# UNO-TH_Rev3e.net
KiCad netlist of a schematic drawn in Altium Designer
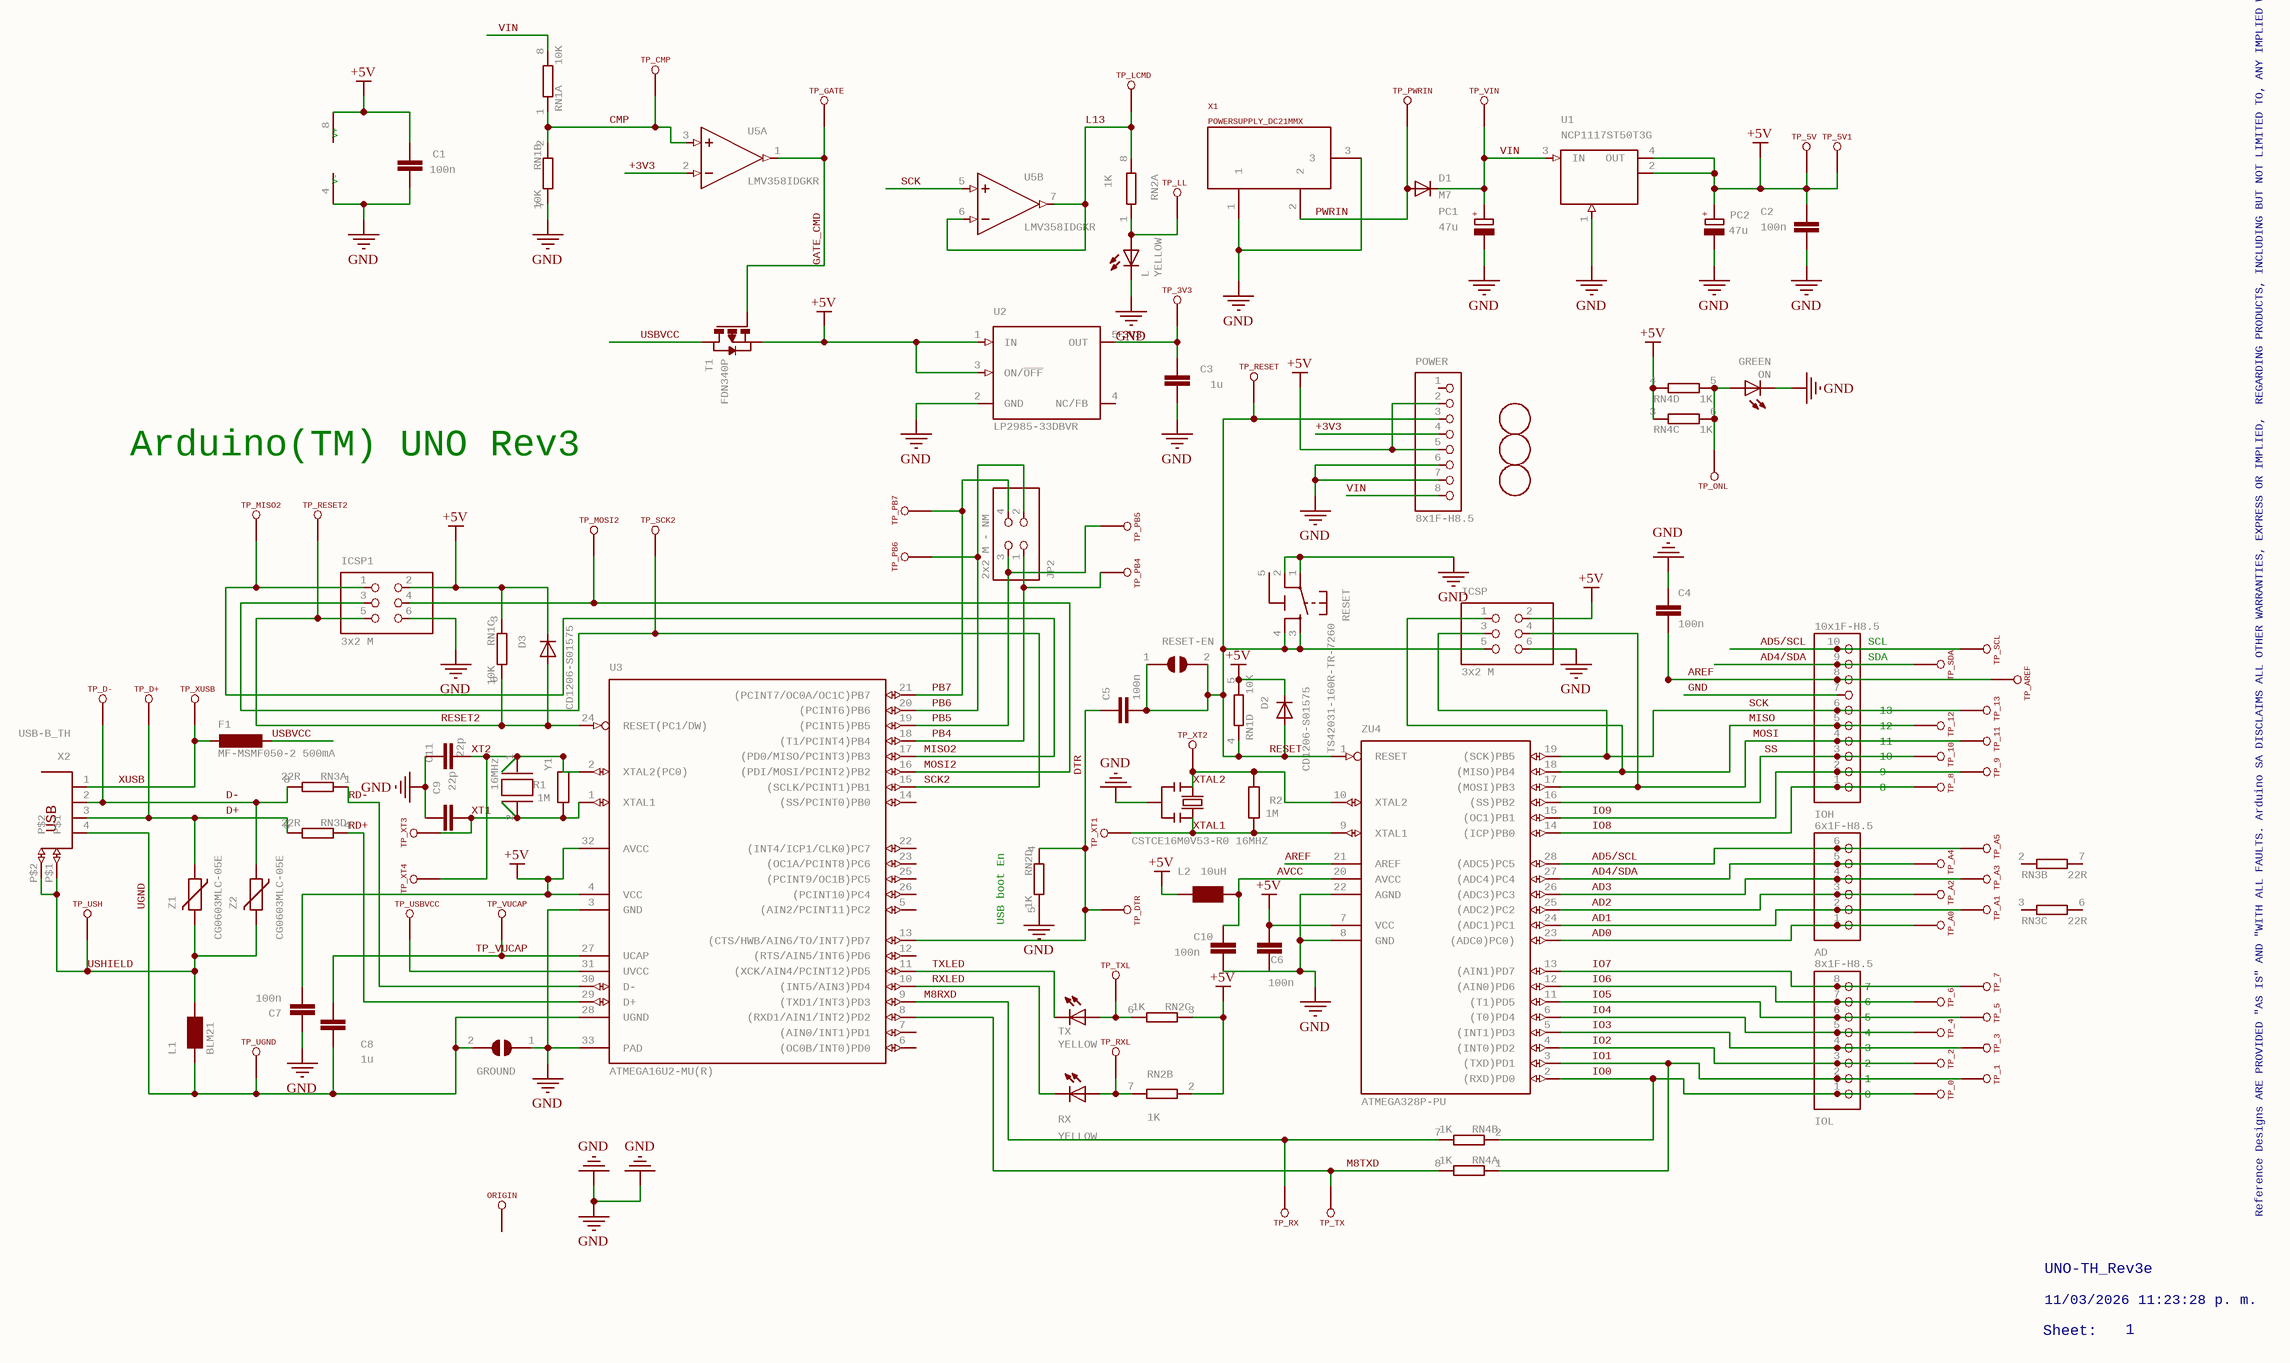
[diagram p0: UNO-TH_Rev3e.SchDoc]

(export (version "E")
  (design (tool "Eeschema 10.0.6"))
  (components
    (comp (ref "AD")
      (value "6x1F-H8.5")
      (footprint "1X06")
      (description "PIN HEADER")
      (libsource (lib "SmartPrj") (part "PINHD-1X6"))
    )
    (comp (ref "C1")
      (value "100n")
      (footprint "C0603-ROUND")
      (description "CAPACITOR, European symbol")
      (libsource (lib "") (part "C-EU0603-RND_3"))
    )
    (comp (ref "C2")
      (value "100n")
      (footprint "C0603-ROUND")
      (description "CAPACITOR, European symbol")
      (libsource (lib "") (part "C-EU0603-RND_2"))
    )
    (comp (ref "C3")
      (value "1u")
      (footprint "C0603-ROUND")
      (description "CAPACITOR, European symbol")
      (libsource (lib "") (part "C-EU0603-RND_3"))
    )
    (comp (ref "C4")
      (value "100n")
      (footprint "C0603-ROUND")
      (description "CAPACITOR, European symbol")
      (libsource (lib "") (part "C-EU0603-RND_1"))
    )
    (comp (ref "C5")
      (value "100n")
      (footprint "C0603-ROUND")
      (description "CAPACITOR, European symbol")
      (libsource (lib "") (part "C-EU0603-RND_3"))
    )
    (comp (ref "C6")
      (value "100n")
      (footprint "C0603-ROUND")
      (description "CAPACITOR, European symbol")
      (libsource (lib "") (part "C-EU0603-RND_2"))
    )
    (comp (ref "C7")
      (value "100n")
      (footprint "C0603-ROUND")
      (description "CAPACITOR, European symbol")
      (libsource (lib "SmartPrj") (part "C-EU0603-RND"))
    )
    (comp (ref "C8")
      (value "1u")
      (footprint "C0603-ROUND")
      (description "CAPACITOR, European symbol")
      (libsource (lib "SmartPrj") (part "C-EU0603-RND"))
    )
    (comp (ref "C9")
      (value "22p")
      (footprint "C0603-ROUND")
      (description "CAPACITOR, European symbol")
      (libsource (lib "") (part "C-EU0603-RND_1"))
    )
    (comp (ref "C10")
      (value "100n")
      (footprint "C0603-ROUND")
      (description "CAPACITOR, European symbol")
      (libsource (lib "") (part "C-EU0603-RND_2"))
    )
    (comp (ref "C11")
      (value "22p")
      (footprint "C0603-ROUND")
      (description "CAPACITOR, European symbol")
      (libsource (lib "") (part "C-EU0603-RND_1"))
    )
    (comp (ref "D1")
      (value "M7")
      (footprint "SMB")
      (description "DIODE")
      (libsource (lib "diode") (part "DIODE-SMB"))
    )
    (comp (ref "D2")
      (value "CD1206-S01575")
      (footprint "MINIMELF")
      (description "DIODE")
      (libsource (lib "diode") (part "DIODE-MINIMELF"))
    )
    (comp (ref "D3")
      (value "CD1206-S01575")
      (footprint "MINIMELF")
      (description "DIODE")
      (libsource (lib "diode") (part "DIODE-MINIMELF"))
    )
    (comp (ref "F1")
      (value "MF-MSMF050-2 500mA")
      (footprint "L1812")
      (description "INDUCTOR, European symbol")
      (libsource (lib "rcl") (part "L-EUL1812"))
    )
    (comp (ref "FD1")
      (value "FIDUCIALMOUNT")
      (footprint "FIDUCIA-MOUNT")
      (libsource (lib "SmartPrj") (part "FIDUCIALMOUNT"))
    )
    (comp (ref "FD2")
      (value "FIDUCIALMOUNT")
      (footprint "FIDUCIA-MOUNT")
      (libsource (lib "SmartPrj") (part "FIDUCIALMOUNT"))
    )
    (comp (ref "FD3")
      (value "FIDUCIALMOUNT")
      (footprint "FIDUCIA-MOUNT")
      (libsource (lib "SmartPrj") (part "FIDUCIALMOUNT"))
    )
    (comp (ref "GROUND")
      (value "SJ")
      (footprint "SJ")
      (description "SMD solder JUMPER")
      (libsource (lib "jumper") (part "SJ"))
    )
    (comp (ref "ICSP")
      (value "3x2 M")
      (footprint "2X03")
      (description "PIN HEADER")
      (libsource (lib "SmartPrj") (part "PINHD-2X3"))
    )
    (comp (ref "ICSP1")
      (value "3x2 M")
      (footprint "2X03")
      (description "PIN HEADER")
      (libsource (lib "SmartPrj") (part "PINHD-2X3"))
    )
    (comp (ref "IOH")
      (value "10x1F-H8.5")
      (footprint "1X10")
      (description "PIN HEADER")
      (libsource (lib "SmartPrj") (part "PINHD-1X10_ARD"))
    )
    (comp (ref "IOL")
      (value "8x1F-H8.5")
      (footprint "1X08")
      (description "PIN HEADER")
      (libsource (lib "SmartPrj") (part "PINHD-1X8"))
    )
    (comp (ref "JP2")
      (value "2x2 M - NM")
      (footprint "2X02")
      (description "PIN HEADER")
      (libsource (lib "SmartPrj") (part "PINHD-2X2"))
    )
    (comp (ref "L")
      (value "YELLOW")
      (footprint "CHIP-LED0805")
      (libsource (lib "led") (part "LEDCHIP-LED0805"))
    )
    (comp (ref "L1")
      (value "BLM21")
      (footprint "0805")
      (libsource (lib "wuerth-elektronik") (part "WE-CBF_0805"))
    )
    (comp (ref "L2")
      (value "10uH")
      (footprint "0805")
      (description "10uH 0805")
      (fields (field (name "PART_NUMBER") "CV201210-100K"))
      (libsource (lib "Induttanze") (part "0715_CV201210-100K"))
    )
    (comp (ref "ON")
      (value "GREEN")
      (footprint "CHIP-LED0805")
      (libsource (lib "led") (part "LEDCHIP-LED0805"))
    )
    (comp (ref "ORIGIN") (value "TP_SP") (footprint "TP-SP") (libsource (lib "SmartPrj") (part "TP_SP")))
    (comp (ref "PC1")
      (value "47u")
      (footprint "PANASONIC_D")
      (description "POLARIZED CAPACITOR, European symbol")
      (fields (field (name "+") "+"))
      (libsource (lib "rcl") (part "CPOL-EUD"))
    )
    (comp (ref "PC2")
      (value "47u")
      (footprint "PANASONIC_D")
      (description "POLARIZED CAPACITOR, European symbol")
      (fields (field (name "+") "+"))
      (libsource (lib "rcl") (part "CPOL-EUD"))
    )
    (comp (ref "POWER")
      (value "8x1F-H8.5")
      (footprint "1X08")
      (description "PIN HEADER")
      (libsource (lib "SmartPrj") (part "PINHD-1X8"))
    )
    (comp (ref "R1")
      (value "1M")
      (footprint "R0603-ROUND")
      (description "RESISTOR, European symbol")
      (libsource (lib "SmartPrj") (part "R-EU_R0603"))
    )
    (comp (ref "R2")
      (value "1M")
      (footprint "R0603-ROUND")
      (description "RESISTOR, European symbol")
      (libsource (lib "SmartPrj") (part "R-EU_R0603"))
    )
    (comp (ref "RESET")
      (value "TS42031-160R-TR-7260")
      (footprint "TS42")
      (description "TS42 Dongnan Electronics Tact switch VDC 12V - 50mA")
      (libsource (lib "SmartPrj") (part "TS42"))
    )
    (comp (ref "RESET-EN")
      (value "SJ")
      (footprint "SJ")
      (description "SMD solder JUMPER")
      (libsource (lib "jumper") (part "SJ"))
    )
    (comp (ref "RN1")
      (value "10K")
      (footprint "CAY16")
      (description "Array Chip Resistor   Source: RS Component / Phycomp")
      (libsource (lib "resistor-dil") (part "4R-NCAY16"))
    )
    (comp (ref "RN2")
      (value "1K")
      (footprint "CAY16")
      (description "Array Chip Resistor   Source: RS Component / Phycomp")
      (libsource (lib "resistor-dil") (part "4R-NCAY16"))
    )
    (comp (ref "RN3")
      (value "22R")
      (footprint "CAY16")
      (description "Array Chip Resistor   Source: RS Component / Phycomp")
      (libsource (lib "resistor-dil") (part "4R-NCAY16"))
    )
    (comp (ref "RN4")
      (value "1K")
      (footprint "CAY16")
      (description "Array Chip Resistor   Source: RS Component / Phycomp")
      (libsource (lib "resistor-dil") (part "4R-NCAY16"))
    )
    (comp (ref "RX")
      (value "YELLOW")
      (footprint "CHIP-LED0805")
      (libsource (lib "led") (part "LEDCHIP-LED0805"))
    )
    (comp (ref "T1")
      (value "FDN340P")
      (footprint "SOT-23")
      (description "MOS FET")
      (libsource (lib "zetex") (part "PMOSSOT23"))
    )
    (comp (ref "TP_0") (value "TP_SP") (footprint "TP-SP") (libsource (lib "SmartPrj") (part "TP_SP")))
    (comp (ref "TP_1") (value "TP_SP") (footprint "TP-SP") (libsource (lib "SmartPrj") (part "TP_SP")))
    (comp (ref "TP_2") (value "TP_SP") (footprint "TP-SP") (libsource (lib "SmartPrj") (part "TP_SP")))
    (comp (ref "TP_3") (value "TP_SP") (footprint "TP-SP") (libsource (lib "SmartPrj") (part "TP_SP")))
    (comp (ref "TP_3V3") (value "TP_SP") (footprint "TP-SP") (libsource (lib "SmartPrj") (part "TP_SP")))
    (comp (ref "TP_4") (value "TP_SP") (footprint "TP-SP") (libsource (lib "SmartPrj") (part "TP_SP")))
    (comp (ref "TP_5") (value "TP_SP") (footprint "TP-SP") (libsource (lib "SmartPrj") (part "TP_SP")))
    (comp (ref "TP_5V") (value "TP_SP") (footprint "TP-SP") (libsource (lib "SmartPrj") (part "TP_SP")))
    (comp (ref "TP_5V1") (value "TP_SP") (footprint "TP-SP") (libsource (lib "SmartPrj") (part "TP_SP")))
    (comp (ref "TP_6") (value "TP_SP") (footprint "TP-SP") (libsource (lib "SmartPrj") (part "TP_SP")))
    (comp (ref "TP_7") (value "TP_SP") (footprint "TP-SP") (libsource (lib "SmartPrj") (part "TP_SP")))
    (comp (ref "TP_8") (value "TP_SP") (footprint "TP-SP") (libsource (lib "SmartPrj") (part "TP_SP")))
    (comp (ref "TP_9") (value "TP_SP") (footprint "TP-SP") (libsource (lib "SmartPrj") (part "TP_SP")))
    (comp (ref "TP_10") (value "TP_SP") (footprint "TP-SP") (libsource (lib "SmartPrj") (part "TP_SP")))
    (comp (ref "TP_11") (value "TP_SP") (footprint "TP-SP") (libsource (lib "SmartPrj") (part "TP_SP")))
    (comp (ref "TP_12") (value "TP_SP") (footprint "TP-SP") (libsource (lib "SmartPrj") (part "TP_SP")))
    (comp (ref "TP_13") (value "TP_SP") (footprint "TP-SP") (libsource (lib "SmartPrj") (part "TP_SP")))
    (comp (ref "TP_A0") (value "TP_SP") (footprint "TP-SP") (libsource (lib "SmartPrj") (part "TP_SP")))
    (comp (ref "TP_A1") (value "TP_SP") (footprint "TP-SP") (libsource (lib "SmartPrj") (part "TP_SP")))
    (comp (ref "TP_A2") (value "TP_SP") (footprint "TP-SP") (libsource (lib "SmartPrj") (part "TP_SP")))
    (comp (ref "TP_A3") (value "TP_SP") (footprint "TP-SP") (libsource (lib "SmartPrj") (part "TP_SP")))
    (comp (ref "TP_A4") (value "TP_SP") (footprint "TP-SP") (libsource (lib "SmartPrj") (part "TP_SP")))
    (comp (ref "TP_A5") (value "TP_SP") (footprint "TP-SP") (libsource (lib "SmartPrj") (part "TP_SP")))
    (comp (ref "TP_AREF") (value "TP_SP") (footprint "TP-SP") (libsource (lib "SmartPrj") (part "TP_SP")))
    (comp (ref "TP_CMP") (value "TP_SP") (footprint "TP-SP") (libsource (lib "SmartPrj") (part "TP_SP")))
    (comp (ref "TP_D+") (value "TP_SP") (footprint "TP-SP") (libsource (lib "SmartPrj") (part "TP_SP")))
    (comp (ref "TP_D-") (value "TP_SP") (footprint "TP-SP") (libsource (lib "SmartPrj") (part "TP_SP")))
    (comp (ref "TP_DTR") (value "TP_SP") (footprint "TP-SP") (libsource (lib "SmartPrj") (part "TP_SP")))
    (comp (ref "TP_GATE") (value "TP_SP") (footprint "TP-SP") (libsource (lib "SmartPrj") (part "TP_SP")))
    (comp (ref "TP_LCMD") (value "TP_SP") (footprint "TP-SP") (libsource (lib "SmartPrj") (part "TP_SP")))
    (comp (ref "TP_LL") (value "TP_SP") (footprint "TP-SP") (libsource (lib "SmartPrj") (part "TP_SP")))
    (comp (ref "TP_MISO2") (value "TP_SP") (footprint "TP-SP") (libsource (lib "SmartPrj") (part "TP_SP")))
    (comp (ref "TP_MOSI2") (value "TP_SP") (footprint "TP-SP") (libsource (lib "SmartPrj") (part "TP_SP")))
    (comp (ref "TP_ONL") (value "TP_SP") (footprint "TP-SP") (libsource (lib "SmartPrj") (part "TP_SP")))
    (comp (ref "TP_PB4") (value "TP_SP") (footprint "TP-SP") (libsource (lib "SmartPrj") (part "TP_SP")))
    (comp (ref "TP_PB5") (value "TP_SP") (footprint "TP-SP") (libsource (lib "SmartPrj") (part "TP_SP")))
    (comp (ref "TP_PB6") (value "TP_SP") (footprint "TP-SP") (libsource (lib "SmartPrj") (part "TP_SP")))
    (comp (ref "TP_PB7") (value "TP_SP") (footprint "TP-SP") (libsource (lib "SmartPrj") (part "TP_SP")))
    (comp (ref "TP_PWRIN") (value "TP_SP") (footprint "TP-SP") (libsource (lib "SmartPrj") (part "TP_SP")))
    (comp (ref "TP_RESET") (value "TP_SP") (footprint "TP-SP") (libsource (lib "SmartPrj") (part "TP_SP")))
    (comp (ref "TP_RESET2") (value "TP_SP") (footprint "TP-SP") (libsource (lib "SmartPrj") (part "TP_SP")))
    (comp (ref "TP_RX") (value "TP_SP") (footprint "TP-SP") (libsource (lib "SmartPrj") (part "TP_SP")))
    (comp (ref "TP_RXL") (value "TP_SP") (footprint "TP-SP") (libsource (lib "SmartPrj") (part "TP_SP")))
    (comp (ref "TP_SCK2") (value "TP_SP") (footprint "TP-SP") (libsource (lib "SmartPrj") (part "TP_SP")))
    (comp (ref "TP_SCL") (value "TP_SP") (footprint "TP-SP") (libsource (lib "SmartPrj") (part "TP_SP")))
    (comp (ref "TP_SDA") (value "TP_SP") (footprint "TP-SP") (libsource (lib "SmartPrj") (part "TP_SP")))
    (comp (ref "TP_TX") (value "TP_SP") (footprint "TP-SP") (libsource (lib "SmartPrj") (part "TP_SP")))
    (comp (ref "TP_TXL") (value "TP_SP") (footprint "TP-SP") (libsource (lib "SmartPrj") (part "TP_SP")))
    (comp (ref "TP_UGND") (value "TP_SP") (footprint "TP-SP") (libsource (lib "SmartPrj") (part "TP_SP")))
    (comp (ref "TP_USBVCC") (value "TP_SP") (footprint "TP-SP") (libsource (lib "SmartPrj") (part "TP_SP")))
    (comp (ref "TP_USH") (value "TP_SP") (footprint "TP-SP") (libsource (lib "SmartPrj") (part "TP_SP")))
    (comp (ref "TP_VIN") (value "TP_SP") (footprint "TP-SP") (libsource (lib "SmartPrj") (part "TP_SP")))
    (comp (ref "TP_VUCAP") (value "TP_SP") (footprint "TP-SP") (libsource (lib "SmartPrj") (part "TP_SP")))
    (comp (ref "TP_XT1") (value "TP_SP") (footprint "TP-SP") (libsource (lib "SmartPrj") (part "TP_SP")))
    (comp (ref "TP_XT2") (value "TP_SP") (footprint "TP-SP") (libsource (lib "SmartPrj") (part "TP_SP")))
    (comp (ref "TP_XT3") (value "TP_SP") (footprint "TP-SP") (libsource (lib "SmartPrj") (part "TP_SP")))
    (comp (ref "TP_XT4") (value "TP_SP") (footprint "TP-SP") (libsource (lib "SmartPrj") (part "TP_SP")))
    (comp (ref "TP_XUSB") (value "TP_SP") (footprint "TP-SP") (libsource (lib "SmartPrj") (part "TP_SP")))
    (comp (ref "TX")
      (value "YELLOW")
      (footprint "CHIP-LED0805")
      (libsource (lib "led") (part "LEDCHIP-LED0805"))
    )
    (comp (ref "U1")
      (value "NCP1117ST50T3G")
      (footprint "SOT223")
      (libsource (lib "linear") (part "MC33269ST*"))
    )
    (comp (ref "U2")
      (value "LP2985-33DBVR")
      (footprint "SOT23-DBV")
      (libsource (lib "SmartPrj") (part "LP2985-XXDBVR"))
    )
    (comp (ref "U3")
      (value "ATMEGA16U2-MU(R)")
      (footprint "MLF32")
      (libsource (lib "SmartPrj") (part "ATMEGA16U2-MU"))
    )
    (comp (ref "U5")
      (value "LMV358IDGKR")
      (footprint "MSOP08")
      (fields (field (name "V+") "V+") (field (name "V-") "V-"))
      (libsource (lib "linear") (part "LMV358?*MM"))
    )
    (comp (ref "X1")
      (value "POWERSUPPLY_DC21MMX")
      (footprint "POWERSUPPLY_DC-21MM")
      (libsource (lib "SmartPrj") (part "POWERSUPPLY_DC21MMX"))
    )
    (comp (ref "X2")
      (value "USB-B_TH")
      (footprint "PN61729")
      (description "BERG USB connector")
      (fields (field (name "USB") "USB"))
      (libsource (lib "SmartPrj") (part "PN61729"))
    )
    (comp (ref "Y1")
      (value "16MHz")
      (footprint "QS")
      (description "CRYSTAL")
      (libsource (lib "SmartPrj") (part "XTAL/S"))
    )
    (comp (ref "Y2")
      (value "CSTCE16M0V53-R0 16MHZ")
      (footprint "RESONATOR")
      (libsource (lib "SmartPrj") (part "RESONATORMU"))
    )
    (comp (ref "Z1")
      (value "CG0603MLC-05E")
      (footprint "CT/CN0603")
      (description "VARISTOR")
      (libsource (lib "varistor") (part "VARISTORCN0603"))
    )
    (comp (ref "Z2")
      (value "CG0603MLC-05E")
      (footprint "CT/CN0603")
      (description "VARISTOR")
      (libsource (lib "varistor") (part "VARISTORCN0603"))
    )
    (comp (ref "ZU4")
      (value "ATMEGA328P-PU")
      (footprint "DIL28-3")
      (description "MICROCONTROLLER   4 Kbytes FLASH   128 bytes SRAM   256 bytes EEPROM   UART   6-channel 10 bit ADC")
      (libsource (lib "SmartPrj") (part "ATMEGA328P-PU"))
    )
  )
  (nets
    (net (code "1") (name "+5V") (class "Default")
      (node (ref "C1") (pin "2") (pinfunction "2_2") (pintype "passive"))
      (node (ref "C2") (pin "2") (pinfunction "2_2") (pintype "passive"))
      (node (ref "C6") (pin "2") (pinfunction "2_2") (pintype "passive"))
      (node (ref "C7") (pin "1") (pinfunction "1_1") (pintype "passive"))
      (node (ref "D2") (pin "C") (pinfunction "C_C") (pintype "passive"))
      (node (ref "D3") (pin "C") (pinfunction "C_C") (pintype "passive"))
      (node (ref "ICSP") (pin "2") (pinfunction "2_2") (pintype "passive"))
      (node (ref "ICSP1") (pin "2") (pinfunction "2_2") (pintype "passive"))
      (node (ref "L2") (pin "1") (pinfunction "1_1") (pintype "passive"))
      (node (ref "PC2") (pin "+") (pinfunction "+_+") (pintype "passive"))
      (node (ref "POWER") (pin "2") (pinfunction "2_2") (pintype "passive"))
      (node (ref "POWER") (pin "5") (pinfunction "5_5") (pintype "passive"))
      (node (ref "RN1") (pin "3") (pinfunction "1_3") (pintype "passive"))
      (node (ref "RN1") (pin "5") (pinfunction "2_5") (pintype "passive"))
      (node (ref "RN2") (pin "2") (pinfunction "1_2") (pintype "passive"))
      (node (ref "RN2") (pin "3") (pinfunction "1_3") (pintype "passive"))
      (node (ref "RN4") (pin "3") (pinfunction "1_3") (pintype "passive"))
      (node (ref "RN4") (pin "4") (pinfunction "1_4") (pintype "passive"))
      (node (ref "T1") (pin "2") (pinfunction "S_2") (pintype "passive"))
      (node (ref "TP_5V") (pin "X") (pinfunction "TESTP_X") (pintype "passive"))
      (node (ref "TP_5V1") (pin "X") (pinfunction "TESTP_X") (pintype "passive"))
      (node (ref "U1") (pin "2") (pinfunction "OUT_2") (pintype "passive"))
      (node (ref "U1") (pin "4") (pinfunction "OUT_4") (pintype "passive"))
      (node (ref "U2") (pin "1") (pinfunction "IN_1") (pintype "input"))
      (node (ref "U2") (pin "3") (pinfunction "ON/~{OFF}_3") (pintype "input"))
      (node (ref "U3") (pin "32") (pinfunction "AVCC_32") (pintype "power_in"))
      (node (ref "U3") (pin "4") (pinfunction "VCC_4") (pintype "power_in"))
      (node (ref "U5") (pin "8") (pinfunction "V+_8") (pintype "power_in"))
      (node (ref "ZU4") (pin "7") (pinfunction "VCC_7") (pintype "power_in"))
    )
    (net (code "2") (name "/+3V3") (class "Default")
      (node (ref "C3") (pin "2") (pinfunction "2_2") (pintype "passive"))
      (node (ref "POWER") (pin "4") (pinfunction "4_4") (pintype "passive"))
      (node (ref "TP_3V3") (pin "X") (pinfunction "TESTP_X") (pintype "passive"))
      (node (ref "U2") (pin "5") (pinfunction "OUT_5") (pintype "passive"))
      (node (ref "U5") (pin "2") (pinfunction "-IN_2") (pintype "input"))
    )
    (net (code "3") (name "/AD0") (class "Default")
      (node (ref "AD") (pin "1") (pinfunction "1_1") (pintype "passive"))
      (node (ref "TP_A0") (pin "X") (pinfunction "TESTP_X") (pintype "passive"))
      (node (ref "ZU4") (pin "23") (pinfunction "(ADC0)PC0)_23") (pintype "bidirectional"))
    )
    (net (code "4") (name "/AD1") (class "Default")
      (node (ref "AD") (pin "2") (pinfunction "2_2") (pintype "passive"))
      (node (ref "TP_A1") (pin "X") (pinfunction "TESTP_X") (pintype "passive"))
      (node (ref "ZU4") (pin "24") (pinfunction "(ADC1)PC1_24") (pintype "bidirectional"))
    )
    (net (code "5") (name "/AD2") (class "Default")
      (node (ref "AD") (pin "3") (pinfunction "3_3") (pintype "passive"))
      (node (ref "TP_A2") (pin "X") (pinfunction "TESTP_X") (pintype "passive"))
      (node (ref "ZU4") (pin "25") (pinfunction "(ADC2)PC2_25") (pintype "bidirectional"))
    )
    (net (code "6") (name "/AD3") (class "Default")
      (node (ref "AD") (pin "4") (pinfunction "4_4") (pintype "passive"))
      (node (ref "TP_A3") (pin "X") (pinfunction "TESTP_X") (pintype "passive"))
      (node (ref "ZU4") (pin "26") (pinfunction "(ADC3)PC3_26") (pintype "bidirectional"))
    )
    (net (code "7") (name "/AD4{slash}SDA") (class "Default")
      (node (ref "AD") (pin "5") (pinfunction "5_5") (pintype "passive"))
      (node (ref "IOH") (pin "9") (pinfunction "9_9") (pintype "passive"))
      (node (ref "TP_A4") (pin "X") (pinfunction "TESTP_X") (pintype "passive"))
      (node (ref "TP_SDA") (pin "X") (pinfunction "TESTP_X") (pintype "passive"))
      (node (ref "ZU4") (pin "27") (pinfunction "(ADC4)PC4_27") (pintype "bidirectional"))
    )
    (net (code "8") (name "/AD5{slash}SCL") (class "Default")
      (node (ref "AD") (pin "6") (pinfunction "6_6") (pintype "passive"))
      (node (ref "IOH") (pin "10") (pinfunction "10_10") (pintype "passive"))
      (node (ref "TP_A5") (pin "X") (pinfunction "TESTP_X") (pintype "passive"))
      (node (ref "TP_SCL") (pin "X") (pinfunction "TESTP_X") (pintype "passive"))
      (node (ref "ZU4") (pin "28") (pinfunction "(ADC5)PC5_28") (pintype "bidirectional"))
    )
    (net (code "9") (name "/AREF") (class "Default")
      (node (ref "C4") (pin "2") (pinfunction "2_2") (pintype "passive"))
      (node (ref "IOH") (pin "8") (pinfunction "8_8") (pintype "passive"))
      (node (ref "TP_AREF") (pin "X") (pinfunction "TESTP_X") (pintype "passive"))
      (node (ref "ZU4") (pin "21") (pinfunction "AREF_21") (pintype "passive"))
    )
    (net (code "10") (name "/AVCC") (class "Default")
      (node (ref "C10") (pin "2") (pinfunction "2_2") (pintype "passive"))
      (node (ref "L2") (pin "2") (pinfunction "2_2") (pintype "passive"))
      (node (ref "ZU4") (pin "20") (pinfunction "AVCC_20") (pintype "power_in"))
    )
    (net (code "11") (name "/CMP") (class "Default")
      (node (ref "RN1") (pin "1") (pinfunction "1_1") (pintype "passive"))
      (node (ref "RN1") (pin "2") (pinfunction "1_2") (pintype "passive"))
      (node (ref "TP_CMP") (pin "X") (pinfunction "TESTP_X") (pintype "passive"))
      (node (ref "U5") (pin "3") (pinfunction "+IN_3") (pintype "input"))
    )
    (net (code "12") (name "/D+") (class "Default")
      (node (ref "RN3") (pin "5") (pinfunction "2_5") (pintype "passive"))
      (node (ref "TP_D+") (pin "X") (pinfunction "TESTP_X") (pintype "passive"))
      (node (ref "X2") (pin "3") (pinfunction "3_3") (pintype "bidirectional"))
      (node (ref "Z1") (pin "1") (pinfunction "1_1") (pintype "passive"))
    )
    (net (code "13") (name "/D-") (class "Default")
      (node (ref "RN3") (pin "8") (pinfunction "2_8") (pintype "passive"))
      (node (ref "TP_D-") (pin "X") (pinfunction "TESTP_X") (pintype "passive"))
      (node (ref "X2") (pin "2") (pinfunction "2_2") (pintype "bidirectional"))
      (node (ref "Z2") (pin "1") (pinfunction "1_1") (pintype "passive"))
    )
    (net (code "14") (name "/DTR") (class "Default")
      (node (ref "C5") (pin "1") (pinfunction "1_1") (pintype "passive"))
      (node (ref "RN2") (pin "4") (pinfunction "1_4") (pintype "passive"))
      (node (ref "TP_DTR") (pin "X") (pinfunction "TESTP_X") (pintype "passive"))
      (node (ref "U3") (pin "13") (pinfunction "(CTS/HWB/AIN6/TO/INT7)PD7_13") (pintype "bidirectional"))
    )
    (net (code "15") (name "/GATE_CMD") (class "Default")
      (node (ref "T1") (pin "3") (pinfunction "G_3") (pintype "passive"))
      (node (ref "TP_GATE") (pin "X") (pinfunction "TESTP_X") (pintype "passive"))
      (node (ref "U5") (pin "1") (pinfunction "OUT_1") (pintype "output"))
    )
    (net (code "16") (name "/IO0") (class "Default")
      (node (ref "IOL") (pin "1") (pinfunction "1_1") (pintype "passive"))
      (node (ref "RN4") (pin "2") (pinfunction "1_2") (pintype "passive"))
      (node (ref "TP_0") (pin "X") (pinfunction "TESTP_X") (pintype "passive"))
      (node (ref "ZU4") (pin "2") (pinfunction "(RXD)PD0_2") (pintype "bidirectional"))
    )
    (net (code "17") (name "/IO1") (class "Default")
      (node (ref "IOL") (pin "2") (pinfunction "2_2") (pintype "passive"))
      (node (ref "RN4") (pin "1") (pinfunction "1_1") (pintype "passive"))
      (node (ref "TP_1") (pin "X") (pinfunction "TESTP_X") (pintype "passive"))
      (node (ref "ZU4") (pin "3") (pinfunction "(TXD)PD1_3") (pintype "bidirectional"))
    )
    (net (code "18") (name "/IO2") (class "Default")
      (node (ref "IOL") (pin "3") (pinfunction "3_3") (pintype "passive"))
      (node (ref "TP_2") (pin "X") (pinfunction "TESTP_X") (pintype "passive"))
      (node (ref "ZU4") (pin "4") (pinfunction "(INT0)PD2_4") (pintype "bidirectional"))
    )
    (net (code "19") (name "/IO3") (class "Default")
      (node (ref "IOL") (pin "4") (pinfunction "4_4") (pintype "passive"))
      (node (ref "TP_3") (pin "X") (pinfunction "TESTP_X") (pintype "passive"))
      (node (ref "ZU4") (pin "5") (pinfunction "(INT1)PD3_5") (pintype "bidirectional"))
    )
    (net (code "20") (name "/IO4") (class "Default")
      (node (ref "IOL") (pin "5") (pinfunction "5_5") (pintype "passive"))
      (node (ref "TP_4") (pin "X") (pinfunction "TESTP_X") (pintype "passive"))
      (node (ref "ZU4") (pin "6") (pinfunction "(T0)PD4_6") (pintype "bidirectional"))
    )
    (net (code "21") (name "/IO5") (class "Default")
      (node (ref "IOL") (pin "6") (pinfunction "6_6") (pintype "passive"))
      (node (ref "TP_5") (pin "X") (pinfunction "TESTP_X") (pintype "passive"))
      (node (ref "ZU4") (pin "11") (pinfunction "(T1)PD5_11") (pintype "bidirectional"))
    )
    (net (code "22") (name "/IO6") (class "Default")
      (node (ref "IOL") (pin "7") (pinfunction "7_7") (pintype "passive"))
      (node (ref "TP_6") (pin "X") (pinfunction "TESTP_X") (pintype "passive"))
      (node (ref "ZU4") (pin "12") (pinfunction "(AIN0)PD6_12") (pintype "bidirectional"))
    )
    (net (code "23") (name "/IO7") (class "Default")
      (node (ref "IOL") (pin "8") (pinfunction "8_8") (pintype "passive"))
      (node (ref "TP_7") (pin "X") (pinfunction "TESTP_X") (pintype "passive"))
      (node (ref "ZU4") (pin "13") (pinfunction "(AIN1)PD7_13") (pintype "bidirectional"))
    )
    (net (code "24") (name "/IO8") (class "Default")
      (node (ref "IOH") (pin "1") (pinfunction "1_1") (pintype "passive"))
      (node (ref "TP_8") (pin "X") (pinfunction "TESTP_X") (pintype "passive"))
      (node (ref "ZU4") (pin "14") (pinfunction "(ICP)PB0_14") (pintype "bidirectional"))
    )
    (net (code "25") (name "/IO9") (class "Default")
      (node (ref "IOH") (pin "2") (pinfunction "2_2") (pintype "passive"))
      (node (ref "TP_9") (pin "X") (pinfunction "TESTP_X") (pintype "passive"))
      (node (ref "ZU4") (pin "15") (pinfunction "(OC1)PB1_15") (pintype "bidirectional"))
    )
    (net (code "26") (name "/L13") (class "Default")
      (node (ref "RN2") (pin "8") (pinfunction "2_8") (pintype "passive"))
      (node (ref "TP_LCMD") (pin "X") (pinfunction "TESTP_X") (pintype "passive"))
      (node (ref "U5") (pin "6") (pinfunction "-IN_6") (pintype "input"))
      (node (ref "U5") (pin "7") (pinfunction "OUT_7") (pintype "output"))
    )
    (net (code "27") (name "/M8RXD") (class "Default")
      (node (ref "RN4") (pin "7") (pinfunction "2_7") (pintype "passive"))
      (node (ref "TP_RX") (pin "X") (pinfunction "TESTP_X") (pintype "passive"))
      (node (ref "U3") (pin "9") (pinfunction "(TXD1/INT3)PD3_9") (pintype "bidirectional"))
    )
    (net (code "28") (name "/M8TXD") (class "Default")
      (node (ref "RN4") (pin "8") (pinfunction "2_8") (pintype "passive"))
      (node (ref "TP_TX") (pin "X") (pinfunction "TESTP_X") (pintype "passive"))
      (node (ref "U3") (pin "8") (pinfunction "(RXD1/AIN1/INT2)PD2_8") (pintype "bidirectional"))
    )
    (net (code "29") (name "/MISO") (class "Default")
      (node (ref "ICSP") (pin "1") (pinfunction "1_1") (pintype "passive"))
      (node (ref "IOH") (pin "5") (pinfunction "5_5") (pintype "passive"))
      (node (ref "TP_12") (pin "X") (pinfunction "TESTP_X") (pintype "passive"))
      (node (ref "ZU4") (pin "18") (pinfunction "(MISO)PB4_18") (pintype "bidirectional"))
    )
    (net (code "30") (name "/MISO2") (class "Default")
      (node (ref "ICSP1") (pin "1") (pinfunction "1_1") (pintype "passive"))
      (node (ref "TP_MISO2") (pin "X") (pinfunction "TESTP_X") (pintype "passive"))
      (node (ref "U3") (pin "17") (pinfunction "(PD0/MISO/PCINT3)PB3_17") (pintype "bidirectional"))
    )
    (net (code "31") (name "/MOSI") (class "Default")
      (node (ref "ICSP") (pin "4") (pinfunction "4_4") (pintype "passive"))
      (node (ref "IOH") (pin "4") (pinfunction "4_4") (pintype "passive"))
      (node (ref "TP_11") (pin "X") (pinfunction "TESTP_X") (pintype "passive"))
      (node (ref "ZU4") (pin "17") (pinfunction "(MOSI)PB3_17") (pintype "bidirectional"))
    )
    (net (code "32") (name "/MOSI2") (class "Default")
      (node (ref "ICSP1") (pin "4") (pinfunction "4_4") (pintype "passive"))
      (node (ref "TP_MOSI2") (pin "X") (pinfunction "TESTP_X") (pintype "passive"))
      (node (ref "U3") (pin "16") (pinfunction "(PDI/MOSI/PCINT2)PB2_16") (pintype "bidirectional"))
    )
    (net (code "33") (name "/PB4") (class "Default")
      (node (ref "JP2") (pin "1") (pinfunction "1_1") (pintype "passive"))
      (node (ref "TP_PB4") (pin "X") (pinfunction "TESTP_X") (pintype "passive"))
      (node (ref "U3") (pin "18") (pinfunction "(T1/PCINT4)PB4_18") (pintype "bidirectional"))
    )
    (net (code "34") (name "/PB5") (class "Default")
      (node (ref "JP2") (pin "3") (pinfunction "3_3") (pintype "passive"))
      (node (ref "TP_PB5") (pin "X") (pinfunction "TESTP_X") (pintype "passive"))
      (node (ref "U3") (pin "19") (pinfunction "(PCINT5)PB5_19") (pintype "bidirectional"))
    )
    (net (code "35") (name "/PB6") (class "Default")
      (node (ref "JP2") (pin "2") (pinfunction "2_2") (pintype "passive"))
      (node (ref "TP_PB6") (pin "X") (pinfunction "TESTP_X") (pintype "passive"))
      (node (ref "U3") (pin "20") (pinfunction "(PCINT6)PB6_20") (pintype "bidirectional"))
    )
    (net (code "36") (name "/PB7") (class "Default")
      (node (ref "JP2") (pin "4") (pinfunction "4_4") (pintype "passive"))
      (node (ref "TP_PB7") (pin "X") (pinfunction "TESTP_X") (pintype "passive"))
      (node (ref "U3") (pin "21") (pinfunction "(PCINT7/OC0A/OC1C)PB7_21") (pintype "bidirectional"))
    )
    (net (code "37") (name "/PWRIN") (class "Default")
      (node (ref "D1") (pin "A") (pinfunction "A_A") (pintype "passive"))
      (node (ref "TP_PWRIN") (pin "X") (pinfunction "TESTP_X") (pintype "passive"))
      (node (ref "X1") (pin "2") (pinfunction "2_2") (pintype "power_in"))
    )
    (net (code "38") (name "/RD+") (class "Default")
      (node (ref "RN3") (pin "4") (pinfunction "1_4") (pintype "passive"))
      (node (ref "U3") (pin "29") (pinfunction "D+_29") (pintype "bidirectional"))
    )
    (net (code "39") (name "/RD-") (class "Default")
      (node (ref "RN3") (pin "1") (pinfunction "1_1") (pintype "passive"))
      (node (ref "U3") (pin "30") (pinfunction "D-_30") (pintype "bidirectional"))
    )
    (net (code "40") (name "/RESET") (class "Default")
      (node (ref "C5") (pin "2") (pinfunction "2_2") (pintype "passive"))
      (node (ref "D2") (pin "A") (pinfunction "A_A") (pintype "passive"))
      (node (ref "ICSP") (pin "5") (pinfunction "5_5") (pintype "passive"))
      (node (ref "POWER") (pin "3") (pinfunction "3_3") (pintype "passive"))
      (node (ref "RESET") (pin "3") (pinfunction "3_3") (pintype "passive"))
      (node (ref "RESET") (pin "4") (pinfunction "4_4") (pintype "passive"))
      (node (ref "RESET-EN") (pin "1") (pinfunction "1_1") (pintype "passive"))
      (node (ref "RESET-EN") (pin "2") (pinfunction "2_2") (pintype "passive"))
      (node (ref "RN1") (pin "4") (pinfunction "1_4") (pintype "passive"))
      (node (ref "TP_RESET") (pin "X") (pinfunction "TESTP_X") (pintype "passive"))
      (node (ref "ZU4") (pin "1") (pinfunction "RESET_1") (pintype "input"))
    )
    (net (code "41") (name "/RESET2") (class "Default")
      (node (ref "D3") (pin "A") (pinfunction "A_A") (pintype "passive"))
      (node (ref "ICSP1") (pin "5") (pinfunction "5_5") (pintype "passive"))
      (node (ref "RN1") (pin "6") (pinfunction "2_6") (pintype "passive"))
      (node (ref "TP_RESET2") (pin "X") (pinfunction "TESTP_X") (pintype "passive"))
      (node (ref "U3") (pin "24") (pinfunction "RESET(PC1/DW)_24") (pintype "input"))
    )
    (net (code "42") (name "/RXLED") (class "Default")
      (node (ref "RX") (pin "C") (pinfunction "C_C") (pintype "passive"))
      (node (ref "U3") (pin "10") (pinfunction "(INT5/AIN3)PD4_10") (pintype "bidirectional"))
    )
    (net (code "43") (name "/SCK") (class "Default")
      (node (ref "ICSP") (pin "3") (pinfunction "3_3") (pintype "passive"))
      (node (ref "IOH") (pin "6") (pinfunction "6_6") (pintype "passive"))
      (node (ref "TP_13") (pin "X") (pinfunction "TESTP_X") (pintype "passive"))
      (node (ref "U5") (pin "5") (pinfunction "+IN_5") (pintype "input"))
      (node (ref "ZU4") (pin "19") (pinfunction "(SCK)PB5_19") (pintype "bidirectional"))
    )
    (net (code "44") (name "/SCK2") (class "Default")
      (node (ref "ICSP1") (pin "3") (pinfunction "3_3") (pintype "passive"))
      (node (ref "TP_SCK2") (pin "X") (pinfunction "TESTP_X") (pintype "passive"))
      (node (ref "U3") (pin "15") (pinfunction "(SCLK/PCINT1)PB1_15") (pintype "bidirectional"))
    )
    (net (code "45") (name "/SS") (class "Default")
      (node (ref "IOH") (pin "3") (pinfunction "3_3") (pintype "passive"))
      (node (ref "TP_10") (pin "X") (pinfunction "TESTP_X") (pintype "passive"))
      (node (ref "ZU4") (pin "16") (pinfunction "(SS)PB2_16") (pintype "bidirectional"))
    )
    (net (code "46") (name "/TP_VUCAP") (class "Default")
      (node (ref "C8") (pin "1") (pinfunction "1_1") (pintype "passive"))
      (node (ref "TP_VUCAP") (pin "X") (pinfunction "TESTP_X") (pintype "passive"))
      (node (ref "U3") (pin "27") (pinfunction "UCAP_27") (pintype "passive"))
    )
    (net (code "47") (name "/TXLED") (class "Default")
      (node (ref "TX") (pin "C") (pinfunction "C_C") (pintype "passive"))
      (node (ref "U3") (pin "11") (pinfunction "(XCK/AIN4/PCINT12)PD5_11") (pintype "bidirectional"))
    )
    (net (code "48") (name "/UGND") (class "Default")
      (node (ref "C8") (pin "2") (pinfunction "2_2") (pintype "passive"))
      (node (ref "GROUND") (pin "2") (pinfunction "2_2") (pintype "passive"))
      (node (ref "L1") (pin "1") (pinfunction "1_1") (pintype "passive"))
      (node (ref "TP_UGND") (pin "X") (pinfunction "TESTP_X") (pintype "passive"))
      (node (ref "U3") (pin "28") (pinfunction "UGND_28") (pintype "power_in"))
      (node (ref "X2") (pin "4") (pinfunction "4_4") (pintype "bidirectional"))
    )
    (net (code "49") (name "/USBVCC") (class "Default")
      (node (ref "F1") (pin "1") (pinfunction "1_1") (pintype "passive"))
      (node (ref "T1") (pin "1") (pinfunction "D_1") (pintype "passive"))
    )
    (net (code "50") (name "/USHIELD") (class "Default")
      (node (ref "L1") (pin "2") (pinfunction "2_2") (pintype "passive"))
      (node (ref "TP_USH") (pin "X") (pinfunction "TESTP_X") (pintype "passive"))
      (node (ref "X2") (pin "P$1") (pinfunction "P$1_P$1") (pintype "bidirectional"))
      (node (ref "X2") (pin "P$2") (pinfunction "P$2_P$2") (pintype "bidirectional"))
      (node (ref "Z1") (pin "2") (pinfunction "2_2") (pintype "passive"))
      (node (ref "Z2") (pin "2") (pinfunction "2_2") (pintype "passive"))
    )
    (net (code "51") (name "/VIN") (class "Default")
      (node (ref "D1") (pin "C") (pinfunction "C_C") (pintype "passive"))
      (node (ref "PC1") (pin "+") (pinfunction "+_+") (pintype "passive"))
      (node (ref "POWER") (pin "8") (pinfunction "8_8") (pintype "passive"))
      (node (ref "RN1") (pin "8") (pinfunction "2_8") (pintype "passive"))
      (node (ref "TP_VIN") (pin "X") (pinfunction "TESTP_X") (pintype "passive"))
      (node (ref "U1") (pin "3") (pinfunction "IN_3") (pintype "input"))
    )
    (net (code "52") (name "/XT1") (class "Default")
      (node (ref "C9") (pin "1") (pinfunction "1_1") (pintype "passive"))
      (node (ref "R1") (pin "1") (pinfunction "1_1") (pintype "passive"))
      (node (ref "TP_XT3") (pin "X") (pinfunction "TESTP_X") (pintype "passive"))
      (node (ref "U3") (pin "1") (pinfunction "XTAL1_1") (pintype "bidirectional"))
      (node (ref "Y1") (pin "2") (pinfunction "2_2") (pintype "passive"))
    )
    (net (code "53") (name "/XT2") (class "Default")
      (node (ref "C11") (pin "1") (pinfunction "1_1") (pintype "passive"))
      (node (ref "R1") (pin "2") (pinfunction "2_2") (pintype "passive"))
      (node (ref "TP_XT4") (pin "X") (pinfunction "TESTP_X") (pintype "passive"))
      (node (ref "U3") (pin "2") (pinfunction "XTAL2(PC0)_2") (pintype "bidirectional"))
      (node (ref "Y1") (pin "1") (pinfunction "1_1") (pintype "passive"))
    )
    (net (code "54") (name "/XTAL1") (class "Default")
      (node (ref "R2") (pin "1") (pinfunction "1_1") (pintype "passive"))
      (node (ref "TP_XT1") (pin "X") (pinfunction "TESTP_X") (pintype "passive"))
      (node (ref "Y2") (pin "3") (pinfunction "3_3") (pintype "passive"))
      (node (ref "ZU4") (pin "9") (pinfunction "XTAL1_9") (pintype "bidirectional"))
    )
    (net (code "55") (name "/XTAL2") (class "Default")
      (node (ref "R2") (pin "2") (pinfunction "2_2") (pintype "passive"))
      (node (ref "TP_XT2") (pin "X") (pinfunction "TESTP_X") (pintype "passive"))
      (node (ref "Y2") (pin "1") (pinfunction "1_1") (pintype "passive"))
      (node (ref "ZU4") (pin "10") (pinfunction "XTAL2_10") (pintype "bidirectional"))
    )
    (net (code "56") (name "/XUSB") (class "Default")
      (node (ref "F1") (pin "2") (pinfunction "2_2") (pintype "passive"))
      (node (ref "TP_XUSB") (pin "X") (pinfunction "TESTP_X") (pintype "passive"))
      (node (ref "X2") (pin "1") (pinfunction "1_1") (pintype "bidirectional"))
    )
    (net (code "57") (name "GND") (class "Default")
      (node (ref "C1") (pin "1") (pinfunction "1_1") (pintype "passive"))
      (node (ref "C10") (pin "1") (pinfunction "1_1") (pintype "passive"))
      (node (ref "C11") (pin "2") (pinfunction "2_2") (pintype "passive"))
      (node (ref "C2") (pin "1") (pinfunction "1_1") (pintype "passive"))
      (node (ref "C3") (pin "1") (pinfunction "1_1") (pintype "passive"))
      (node (ref "C4") (pin "1") (pinfunction "1_1") (pintype "passive"))
      (node (ref "C6") (pin "1") (pinfunction "1_1") (pintype "passive"))
      (node (ref "C7") (pin "2") (pinfunction "2_2") (pintype "passive"))
      (node (ref "C9") (pin "2") (pinfunction "2_2") (pintype "passive"))
      (node (ref "GROUND") (pin "1") (pinfunction "1_1") (pintype "passive"))
      (node (ref "ICSP") (pin "6") (pinfunction "6_6") (pintype "passive"))
      (node (ref "ICSP1") (pin "6") (pinfunction "6_6") (pintype "passive"))
      (node (ref "IOH") (pin "7") (pinfunction "7_7") (pintype "passive"))
      (node (ref "L") (pin "C") (pinfunction "C_C") (pintype "passive"))
      (node (ref "ON") (pin "C") (pinfunction "C_C") (pintype "passive"))
      (node (ref "PC1") (pin "-") (pinfunction "-_-") (pintype "passive"))
      (node (ref "PC2") (pin "-") (pinfunction "-_-") (pintype "passive"))
      (node (ref "POWER") (pin "6") (pinfunction "6_6") (pintype "passive"))
      (node (ref "POWER") (pin "7") (pinfunction "7_7") (pintype "passive"))
      (node (ref "RESET") (pin "1") (pinfunction "1_1") (pintype "passive"))
      (node (ref "RESET") (pin "2") (pinfunction "2_2") (pintype "passive"))
      (node (ref "RN1") (pin "7") (pinfunction "2_7") (pintype "passive"))
      (node (ref "RN2") (pin "5") (pinfunction "2_5") (pintype "passive"))
      (node (ref "U1") (pin "1") (pinfunction "GND/ADJ_1") (pintype "input"))
      (node (ref "U2") (pin "2") (pinfunction "GND_2") (pintype "power_in"))
      (node (ref "U3") (pin "3") (pinfunction "GND_3") (pintype "power_in"))
      (node (ref "U3") (pin "33") (pinfunction "PAD_33") (pintype "power_in"))
      (node (ref "U5") (pin "4") (pinfunction "V-_4") (pintype "power_in"))
      (node (ref "X1") (pin "1") (pinfunction "1_1") (pintype "power_in"))
      (node (ref "X1") (pin "3") (pinfunction "3_3") (pintype "power_in"))
      (node (ref "Y2") (pin "2") (pinfunction "2_2") (pintype "passive"))
      (node (ref "ZU4") (pin "22") (pinfunction "AGND_22") (pintype "power_in"))
      (node (ref "ZU4") (pin "8") (pinfunction "GND_8") (pintype "power_in"))
    )
    (net (code "58") (name "Net-(RN2B-2)") (class "Default")
      (node (ref "RN2") (pin "7") (pinfunction "2_7") (pintype "passive"))
      (node (ref "RX") (pin "A") (pinfunction "A_A") (pintype "passive"))
      (node (ref "TP_RXL") (pin "X") (pinfunction "TESTP_X") (pintype "passive"))
    )
    (net (code "59") (name "Net-(RN2C-2)") (class "Default")
      (node (ref "RN2") (pin "6") (pinfunction "2_6") (pintype "passive"))
      (node (ref "TP_TXL") (pin "X") (pinfunction "TESTP_X") (pintype "passive"))
      (node (ref "TX") (pin "A") (pinfunction "A_A") (pintype "passive"))
    )
    (net (code "60") (name "Net-(RN4C-2)") (class "Default")
      (node (ref "ON") (pin "A") (pinfunction "A_A") (pintype "passive"))
      (node (ref "RN4") (pin "5") (pinfunction "2_5") (pintype "passive"))
      (node (ref "RN4") (pin "6") (pinfunction "2_6") (pintype "passive"))
      (node (ref "TP_ONL") (pin "X") (pinfunction "TESTP_X") (pintype "passive"))
    )
    (net (code "61") (name "Net-(TP_LL-TESTP)") (class "Default")
      (node (ref "L") (pin "A") (pinfunction "A_A") (pintype "passive"))
      (node (ref "RN2") (pin "1") (pinfunction "1_1") (pintype "passive"))
      (node (ref "TP_LL") (pin "X") (pinfunction "TESTP_X") (pintype "passive"))
    )
    (net (code "62") (name "Net-(TP_USBVCC-TESTP)") (class "Default")
      (node (ref "TP_USBVCC") (pin "X") (pinfunction "TESTP_X") (pintype "passive"))
      (node (ref "U3") (pin "31") (pinfunction "UVCC_31") (pintype "power_in"))
    )
    (net (code "63") (name "unconnected-(ORIGIN-TESTP-PadX)") (class "Default")
      (node (ref "ORIGIN") (pin "X") (pinfunction "TESTP_X") (pintype "passive"))
    )
    (net (code "64") (name "unconnected-(POWER-Pad1)") (class "Default")
      (node (ref "POWER") (pin "1") (pinfunction "1_1") (pintype "passive"))
    )
    (net (code "65") (name "unconnected-(RESET-5-GND-Pad5)") (class "Default")
      (node (ref "RESET") (pin "5") (pinfunction "5-GND_5") (pintype "power_in"))
    )
    (net (code "66") (name "unconnected-(RN3B-1-Pad2)") (class "Default")
      (node (ref "RN3") (pin "2") (pinfunction "1_2") (pintype "passive"))
    )
    (net (code "67") (name "unconnected-(RN3B-2-Pad7)") (class "Default")
      (node (ref "RN3") (pin "7") (pinfunction "2_7") (pintype "passive"))
    )
    (net (code "68") (name "unconnected-(RN3C-1-Pad3)") (class "Default")
      (node (ref "RN3") (pin "3") (pinfunction "1_3") (pintype "passive"))
    )
    (net (code "69") (name "unconnected-(RN3C-2-Pad6)") (class "Default")
      (node (ref "RN3") (pin "6") (pinfunction "2_6") (pintype "passive"))
    )
    (net (code "70") (name "unconnected-(U2-NC{slash}FB-Pad4)") (class "Default")
      (node (ref "U2") (pin "4") (pinfunction "NC/FB_4") (pintype "passive"))
    )
    (net (code "71") (name "unconnected-(U3-(AIN0{slash}INT1)PD1-Pad7)") (class "Default")
      (node (ref "U3") (pin "7") (pinfunction "(AIN0/INT1)PD1_7") (pintype "bidirectional"))
    )
    (net (code "72") (name "unconnected-(U3-(AIN2{slash}PCINT11)PC2-Pad5)") (class "Default")
      (node (ref "U3") (pin "5") (pinfunction "(AIN2/PCINT11)PC2_5") (pintype "bidirectional"))
    )
    (net (code "73") (name "unconnected-(U3-(INT4{slash}ICP1{slash}CLK0)PC7-Pad22)") (class "Default")
      (node (ref "U3") (pin "22") (pinfunction "(INT4/ICP1/CLK0)PC7_22") (pintype "bidirectional"))
    )
    (net (code "74") (name "unconnected-(U3-(OC0B{slash}INT0)PD0-Pad6)") (class "Default")
      (node (ref "U3") (pin "6") (pinfunction "(OC0B/INT0)PD0_6") (pintype "bidirectional"))
    )
    (net (code "75") (name "unconnected-(U3-(OC1A{slash}PCINT8)PC6-Pad23)") (class "Default")
      (node (ref "U3") (pin "23") (pinfunction "(OC1A/PCINT8)PC6_23") (pintype "bidirectional"))
    )
    (net (code "76") (name "unconnected-(U3-(PCINT9{slash}OC1B)PC5-Pad25)") (class "Default")
      (node (ref "U3") (pin "25") (pinfunction "(PCINT9/OC1B)PC5_25") (pintype "bidirectional"))
    )
    (net (code "77") (name "unconnected-(U3-(PCINT10)PC4-Pad26)") (class "Default")
      (node (ref "U3") (pin "26") (pinfunction "(PCINT10)PC4_26") (pintype "bidirectional"))
    )
    (net (code "78") (name "unconnected-(U3-(RTS{slash}AIN5{slash}INT6)PD6-Pad12)") (class "Default")
      (node (ref "U3") (pin "12") (pinfunction "(RTS/AIN5/INT6)PD6_12") (pintype "bidirectional"))
    )
    (net (code "79") (name "unconnected-(U3-(SS{slash}PCINT0)PB0-Pad14)") (class "Default")
      (node (ref "U3") (pin "14") (pinfunction "(SS/PCINT0)PB0_14") (pintype "bidirectional"))
    )
  )
)
